# B2B_1.net
KiCad netlist of a schematic drawn in Altium Designer
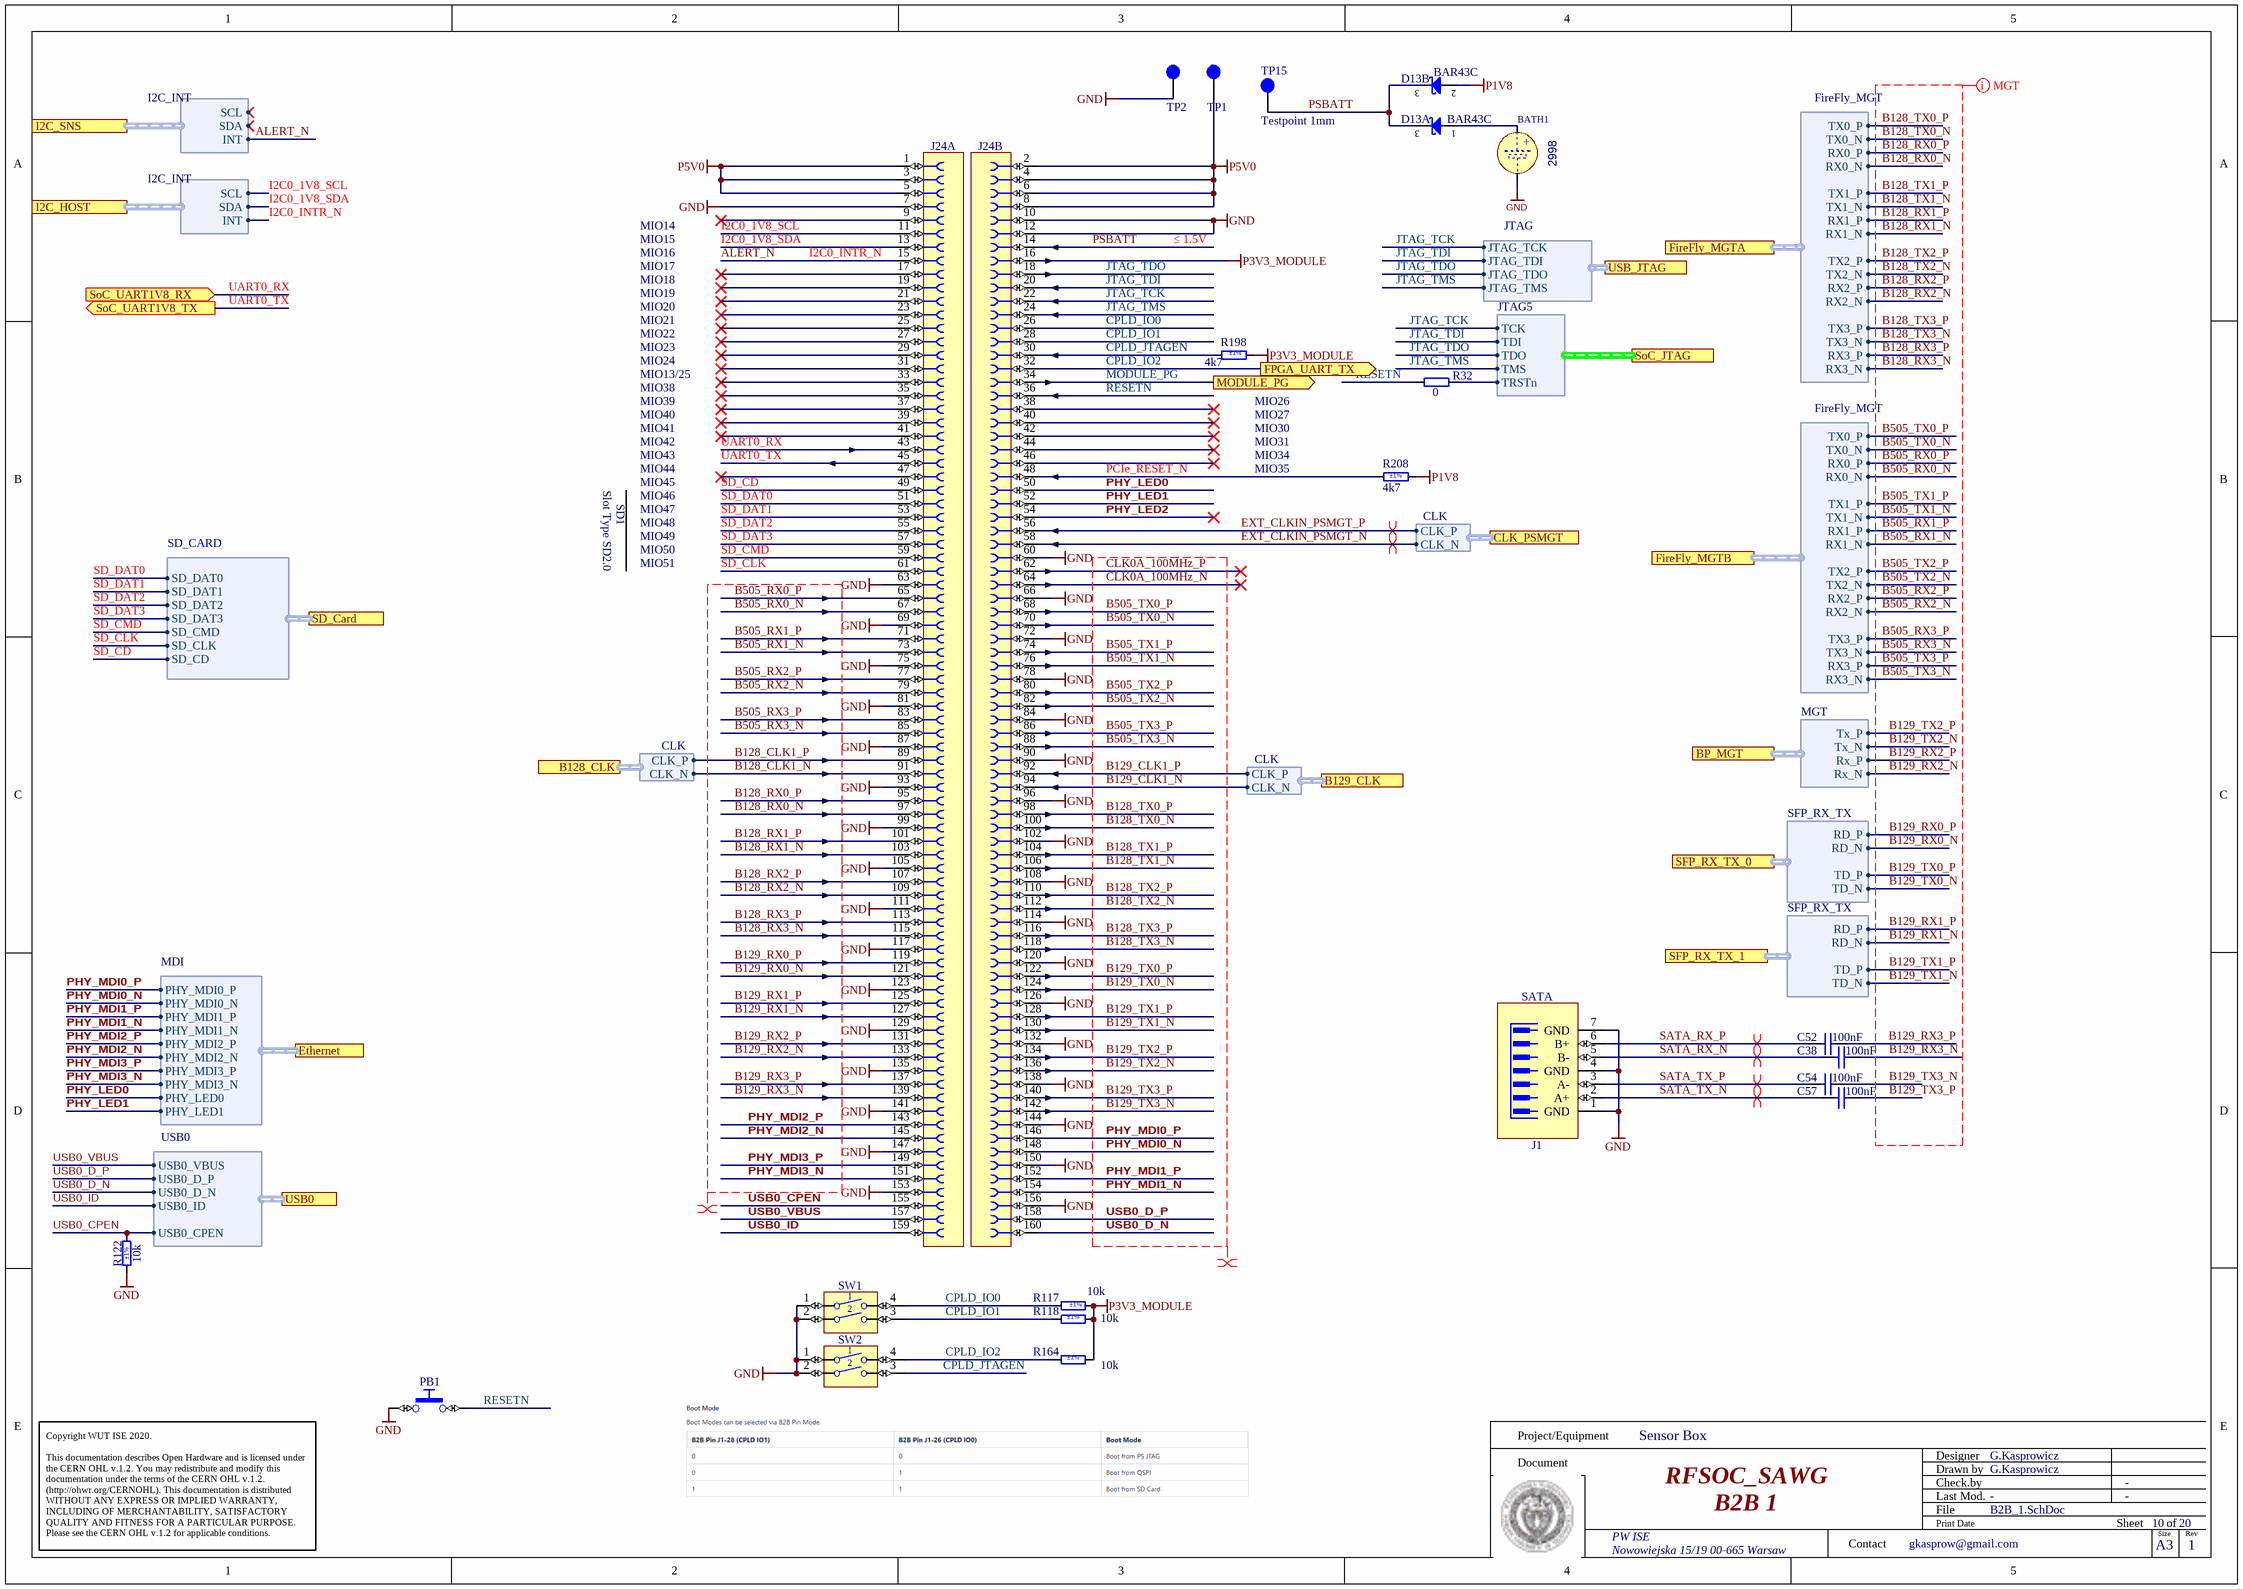
[diagram p0: B2B_1.SchDoc]

(export (version "E")
  (design (tool "Eeschema 10.0.6"))
  (components
    (comp (ref "BATH1")
      (value "~")
      (footprint "BATH_KEYSTONE_2998")
      (description "Battery Holder whit 2 Pin")
      (fields
        (field (name "MANUFACTURER PART NUMBER") "2998")
        (field (name "MANUFACTURER") "KEYSTONE")
        (field (name "PART NUMBER") "BATH_KEYSTONE_2998")
        (field (name "AUTHOR") "CERN DEM JLC")
      )
      (libsource (lib "Eletro-mechanical") (part "Battery Holder 2 Pin"))
    )
    (comp (ref "C38")
      (value "100nF")
      (footprint "CAPC0603X33N")
      (description "Non-polarised capacitor")
      (fields
        (field (name "PART NUMBER") "CC0201_100NF_6.3V_10%_X5R")
        (field (name "VOLTAGE") "6.3V")
        (field (name "AUTHOR") "CERN DEM JLC")
      )
      (libsource (lib "Capacitors") (part "Capacitor - non polarized"))
    )
    (comp (ref "C52")
      (value "100nF")
      (footprint "CAPC0603X33N")
      (description "Non-polarised capacitor")
      (fields
        (field (name "PART NUMBER") "CC0201_100NF_6.3V_10%_X5R")
        (field (name "VOLTAGE") "6.3V")
        (field (name "AUTHOR") "CERN DEM JLC")
      )
      (libsource (lib "Capacitors") (part "Capacitor - non polarized"))
    )
    (comp (ref "C54")
      (value "100nF")
      (footprint "CAPC0603X33N")
      (description "Non-polarised capacitor")
      (fields
        (field (name "PART NUMBER") "CC0201_100NF_6.3V_10%_X5R")
        (field (name "VOLTAGE") "6.3V")
        (field (name "AUTHOR") "CERN DEM JLC")
      )
      (libsource (lib "Capacitors") (part "Capacitor - non polarized"))
    )
    (comp (ref "C57")
      (value "100nF")
      (footprint "CAPC0603X33N")
      (description "Non-polarised capacitor")
      (fields
        (field (name "PART NUMBER") "CC0201_100NF_6.3V_10%_X5R")
        (field (name "VOLTAGE") "6.3V")
        (field (name "AUTHOR") "CERN DEM JLC")
      )
      (libsource (lib "Capacitors") (part "Capacitor - non polarized"))
    )
    (comp (ref "D13")
      (value "BAR43C")
      (footprint "SOT95P240X130-3N")
      (description "Dual Common Cathode Schottky Diodes")
      (fields
        (field (name "VOLTAGE") "30V")
        (field (name "POWER") "200mA")
        (field (name "AUTHOR") "CERN DEM JLC")
      )
      (libsource (lib "ICs And Semiconductors") (part "Diode Schottky x2 A1C3_A2C3"))
    )
    (comp (ref "J1")
      (value "SATA")
      (footprint "MOLEX_67800-5005")
      (description "7 Pin SATA Receptacle")
      (fields
        (field (name "PART NUMBER") "MOLEX_67800-5005")
        (field (name "MANUFACTURER") "MOLEX")
        (field (name "AUTHOR") "CERN DEM MR")
      )
      (libsource (lib "Connectors") (part "Connector SATA 7 Male"))
    )
    (comp (ref "J24")
      (value "Socket 160")
      (footprint "SAMTEC_SS5-80-3.00-L-D-K")
      (description "Connector 160 Female")
      (fields
        (field (name "PART NUMBER") "SAMTEC_SS5-80-3.00-L-D-K")
        (field (name "MANUFACTURER") "SAMTEC")
        (field (name "AUTHOR") "CERN DEM BC")
      )
      (libsource (lib "Connectors") (part "Connector 160 Female"))
    )
    (comp (ref "PB1")
      (value "Push Button")
      (footprint "PB_TYCO_FSMSM")
      (description "Push-Button Switch SPDT")
      (fields
        (field (name "PART NUMBER") "PB_TYCO_FSMSM")
        (field (name "MANUFACTURER") "TYCO ELECTRONICS")
        (field (name "AUTHOR") "CERN DEM JLC")
      )
      (libsource (lib "Eletro-mechanical") (part "PB SPST 1NO-2NO"))
    )
    (comp (ref "R32")
      (value "0")
      (footprint "RESC1005X40N")
      (description "Resistor")
      (fields
        (field (name "PART NUMBER") "R0402_0R_JUMPER")
        (field (name "MANUFACTURER") "GENERIC")
        (field (name "AUTHOR") "CERN DEM JLC")
      )
      (libsource (lib "Resistors") (part "Resistor"))
    )
    (comp (ref "R117")
      (value "10k")
      (footprint "RESC1005X40N")
      (description "Resistor - 1%")
      (fields
        (field (name "TOLERANCE") "±1%")
        (field (name "PART NUMBER") "R0402_10K_1%_0.0625W_100PPM")
        (field (name "POWER") "0.0625W")
        (field (name "AUTHOR") "CERN DEM JLC")
      )
      (libsource (lib "Resistors") (part "Resistor - 1%"))
    )
    (comp (ref "R118")
      (value "10k")
      (footprint "RESC1005X40N")
      (description "Resistor - 1%")
      (fields
        (field (name "TOLERANCE") "±1%")
        (field (name "PART NUMBER") "R0402_10K_1%_0.0625W_100PPM")
        (field (name "POWER") "0.0625W")
        (field (name "AUTHOR") "CERN DEM JLC")
      )
      (libsource (lib "Resistors") (part "Resistor - 1%"))
    )
    (comp (ref "R122")
      (value "10k")
      (footprint "RESC1005X40N")
      (description "Resistor - 1%")
      (fields
        (field (name "TOLERANCE") "±1%")
        (field (name "PART NUMBER") "R0402_10K_1%_0.0625W_100PPM")
        (field (name "POWER") "0.0625W")
        (field (name "AUTHOR") "CERN DEM JLC")
      )
      (libsource (lib "Resistors") (part "Resistor - 1%"))
    )
    (comp (ref "R164")
      (value "10k")
      (footprint "RESC1005X40N")
      (description "Resistor - 1%")
      (fields
        (field (name "TOLERANCE") "±1%")
        (field (name "PART NUMBER") "R0402_10K_1%_0.0625W_100PPM")
        (field (name "POWER") "0.0625W")
        (field (name "AUTHOR") "CERN DEM JLC")
      )
      (libsource (lib "Resistors") (part "Resistor - 1%"))
    )
    (comp (ref "R198")
      (value "4k7")
      (footprint "RESC1005X40N")
      (description "Resistor - 1%")
      (fields
        (field (name "TOLERANCE") "±1%")
        (field (name "PART NUMBER") "R0402_4K7_1%_0.0625W_100PPM")
        (field (name "POWER") "0.0625W")
        (field (name "AUTHOR") "CERN DEM JLC")
      )
      (libsource (lib "Resistors") (part "Resistor - 1%"))
    )
    (comp (ref "R208")
      (value "4k7")
      (footprint "RESC1005X40N")
      (description "Resistor - 1%")
      (fields
        (field (name "TOLERANCE") "±1%")
        (field (name "PART NUMBER") "R0402_4K7_1%_0.0625W_100PPM")
        (field (name "POWER") "0.0625W")
        (field (name "AUTHOR") "CERN DEM JLC")
      )
      (libsource (lib "Resistors") (part "Resistor - 1%"))
    )
    (comp (ref "SW1")
      (value "Switch")
      (footprint "SW_OMRON_A6H-2102")
      (description "2 Ways SPST DIP Switch")
      (fields
        (field (name "PART NUMBER") "SW_OMRON_A6H-2102")
        (field (name "MANUFACTURER") "OMRON")
        (field (name "AUTHOR") "CERN DEM BC")
      )
      (libsource (lib "Eletro-mechanical") (part "SW 2x SPST DIP Switch"))
    )
    (comp (ref "SW2")
      (value "Switch")
      (footprint "SW_OMRON_A6H-2102")
      (description "2 Ways SPST DIP Switch")
      (fields
        (field (name "PART NUMBER") "SW_OMRON_A6H-2102")
        (field (name "MANUFACTURER") "OMRON")
        (field (name "AUTHOR") "CERN DEM BC")
      )
      (libsource (lib "Eletro-mechanical") (part "SW 2x SPST DIP Switch"))
    )
    (comp (ref "TP1") (value "Testpoint 0.8mm") (footprint "TP_0.8mm") (libsource (lib "TE") (part "TP")))
    (comp (ref "TP2") (value "Testpoint 0.8mm") (footprint "TP_0.8mm") (libsource (lib "TE") (part "TP")))
    (comp (ref "TP15") (value "Testpoint 1mm") (footprint "TP_1mm") (libsource (lib "TE") (part "TP")))
  )
  (nets
    (net (code "11") (name "/ALERT_N") (class "Default")
      (node (ref "J24") (pin "15") (pinfunction "15_15") (pintype "bidirectional"))
    )
    (net (code "12") (name "/B128_CLK1_N") (class "Default")
      (node (ref "J24") (pin "91") (pinfunction "91_91") (pintype "bidirectional"))
    )
    (net (code "13") (name "/B128_CLK1_P") (class "Default")
      (node (ref "J24") (pin "89") (pinfunction "89_89") (pintype "bidirectional"))
    )
    (net (code "14") (name "/B128_RX0_N") (class "Default")
      (node (ref "J24") (pin "97") (pinfunction "97_97") (pintype "bidirectional"))
    )
    (net (code "15") (name "/B128_RX0_P") (class "Default")
      (node (ref "J24") (pin "95") (pinfunction "95_95") (pintype "bidirectional"))
    )
    (net (code "16") (name "/B128_RX1_N") (class "Default")
      (node (ref "J24") (pin "103") (pinfunction "103_103") (pintype "bidirectional"))
    )
    (net (code "17") (name "/B128_RX1_P") (class "Default")
      (node (ref "J24") (pin "101") (pinfunction "101_101") (pintype "bidirectional"))
    )
    (net (code "18") (name "/B128_RX2_N") (class "Default")
      (node (ref "J24") (pin "109") (pinfunction "109_109") (pintype "bidirectional"))
    )
    (net (code "19") (name "/B128_RX2_P") (class "Default")
      (node (ref "J24") (pin "107") (pinfunction "107_107") (pintype "bidirectional"))
    )
    (net (code "20") (name "/B128_RX3_N") (class "Default")
      (node (ref "J24") (pin "115") (pinfunction "115_115") (pintype "bidirectional"))
    )
    (net (code "21") (name "/B128_RX3_P") (class "Default")
      (node (ref "J24") (pin "113") (pinfunction "113_113") (pintype "bidirectional"))
    )
    (net (code "22") (name "/B128_TX0_N") (class "Default")
      (node (ref "J24") (pin "100") (pinfunction "100_100") (pintype "bidirectional"))
    )
    (net (code "23") (name "/B128_TX0_P") (class "Default")
      (node (ref "J24") (pin "98") (pinfunction "98_98") (pintype "bidirectional"))
    )
    (net (code "24") (name "/B128_TX1_N") (class "Default")
      (node (ref "J24") (pin "106") (pinfunction "106_106") (pintype "bidirectional"))
    )
    (net (code "25") (name "/B128_TX1_P") (class "Default")
      (node (ref "J24") (pin "104") (pinfunction "104_104") (pintype "bidirectional"))
    )
    (net (code "26") (name "/B128_TX2_N") (class "Default")
      (node (ref "J24") (pin "112") (pinfunction "112_112") (pintype "bidirectional"))
    )
    (net (code "27") (name "/B128_TX2_P") (class "Default")
      (node (ref "J24") (pin "110") (pinfunction "110_110") (pintype "bidirectional"))
    )
    (net (code "28") (name "/B128_TX3_N") (class "Default")
      (node (ref "J24") (pin "118") (pinfunction "118_118") (pintype "bidirectional"))
    )
    (net (code "29") (name "/B128_TX3_P") (class "Default")
      (node (ref "J24") (pin "116") (pinfunction "116_116") (pintype "bidirectional"))
    )
    (net (code "30") (name "/B129_CLK1_N") (class "Default")
      (node (ref "J24") (pin "94") (pinfunction "94_94") (pintype "bidirectional"))
    )
    (net (code "31") (name "/B129_CLK1_P") (class "Default")
      (node (ref "J24") (pin "92") (pinfunction "92_92") (pintype "bidirectional"))
    )
    (net (code "32") (name "/B129_RX0_N") (class "Default")
      (node (ref "J24") (pin "121") (pinfunction "121_121") (pintype "bidirectional"))
    )
    (net (code "33") (name "/B129_RX0_P") (class "Default")
      (node (ref "J24") (pin "119") (pinfunction "119_119") (pintype "bidirectional"))
    )
    (net (code "34") (name "/B129_RX1_N") (class "Default")
      (node (ref "J24") (pin "127") (pinfunction "127_127") (pintype "bidirectional"))
    )
    (net (code "35") (name "/B129_RX1_P") (class "Default")
      (node (ref "J24") (pin "125") (pinfunction "125_125") (pintype "bidirectional"))
    )
    (net (code "36") (name "/B129_RX2_N") (class "Default")
      (node (ref "J24") (pin "133") (pinfunction "133_133") (pintype "bidirectional"))
    )
    (net (code "37") (name "/B129_RX2_P") (class "Default")
      (node (ref "J24") (pin "131") (pinfunction "131_131") (pintype "bidirectional"))
    )
    (net (code "38") (name "/B129_RX3_N") (class "Default")
      (node (ref "C38") (pin "2") (pinfunction "2_2") (pintype "passive"))
      (node (ref "J24") (pin "139") (pinfunction "139_139") (pintype "bidirectional"))
    )
    (net (code "39") (name "/B129_RX3_P") (class "Default")
      (node (ref "C52") (pin "2") (pinfunction "2_2") (pintype "passive"))
      (node (ref "J24") (pin "137") (pinfunction "137_137") (pintype "bidirectional"))
    )
    (net (code "40") (name "/B129_TX0_N") (class "Default")
      (node (ref "J24") (pin "124") (pinfunction "124_124") (pintype "bidirectional"))
    )
    (net (code "41") (name "/B129_TX0_P") (class "Default")
      (node (ref "J24") (pin "122") (pinfunction "122_122") (pintype "bidirectional"))
    )
    (net (code "42") (name "/B129_TX1_N") (class "Default")
      (node (ref "J24") (pin "130") (pinfunction "130_130") (pintype "bidirectional"))
    )
    (net (code "43") (name "/B129_TX1_P") (class "Default")
      (node (ref "J24") (pin "128") (pinfunction "128_128") (pintype "bidirectional"))
    )
    (net (code "44") (name "/B129_TX2_N") (class "Default")
      (node (ref "J24") (pin "136") (pinfunction "136_136") (pintype "bidirectional"))
    )
    (net (code "45") (name "/B129_TX2_P") (class "Default")
      (node (ref "J24") (pin "134") (pinfunction "134_134") (pintype "bidirectional"))
    )
    (net (code "46") (name "/B129_TX3_N") (class "Default")
      (node (ref "C54") (pin "2") (pinfunction "2_2") (pintype "passive"))
      (node (ref "J24") (pin "142") (pinfunction "142_142") (pintype "bidirectional"))
    )
    (net (code "47") (name "/B129_TX3_P") (class "Default")
      (node (ref "C57") (pin "2") (pinfunction "2_2") (pintype "passive"))
      (node (ref "J24") (pin "140") (pinfunction "140_140") (pintype "bidirectional"))
    )
    (net (code "48") (name "/B505_RX0_N") (class "Default")
      (node (ref "J24") (pin "67") (pinfunction "67_67") (pintype "bidirectional"))
    )
    (net (code "49") (name "/B505_RX0_P") (class "Default")
      (node (ref "J24") (pin "65") (pinfunction "65_65") (pintype "bidirectional"))
    )
    (net (code "50") (name "/B505_RX1_N") (class "Default")
      (node (ref "J24") (pin "73") (pinfunction "73_73") (pintype "bidirectional"))
    )
    (net (code "51") (name "/B505_RX1_P") (class "Default")
      (node (ref "J24") (pin "71") (pinfunction "71_71") (pintype "bidirectional"))
    )
    (net (code "52") (name "/B505_RX2_N") (class "Default")
      (node (ref "J24") (pin "79") (pinfunction "79_79") (pintype "bidirectional"))
    )
    (net (code "53") (name "/B505_RX2_P") (class "Default")
      (node (ref "J24") (pin "77") (pinfunction "77_77") (pintype "bidirectional"))
    )
    (net (code "54") (name "/B505_RX3_N") (class "Default")
      (node (ref "J24") (pin "85") (pinfunction "85_85") (pintype "bidirectional"))
    )
    (net (code "55") (name "/B505_RX3_P") (class "Default")
      (node (ref "J24") (pin "83") (pinfunction "83_83") (pintype "bidirectional"))
    )
    (net (code "56") (name "/B505_TX0_N") (class "Default")
      (node (ref "J24") (pin "70") (pinfunction "70_70") (pintype "bidirectional"))
    )
    (net (code "57") (name "/B505_TX0_P") (class "Default")
      (node (ref "J24") (pin "68") (pinfunction "68_68") (pintype "bidirectional"))
    )
    (net (code "58") (name "/B505_TX1_N") (class "Default")
      (node (ref "J24") (pin "76") (pinfunction "76_76") (pintype "bidirectional"))
    )
    (net (code "59") (name "/B505_TX1_P") (class "Default")
      (node (ref "J24") (pin "74") (pinfunction "74_74") (pintype "bidirectional"))
    )
    (net (code "60") (name "/B505_TX2_N") (class "Default")
      (node (ref "J24") (pin "82") (pinfunction "82_82") (pintype "bidirectional"))
    )
    (net (code "61") (name "/B505_TX2_P") (class "Default")
      (node (ref "J24") (pin "80") (pinfunction "80_80") (pintype "bidirectional"))
    )
    (net (code "62") (name "/B505_TX3_N") (class "Default")
      (node (ref "J24") (pin "88") (pinfunction "88_88") (pintype "bidirectional"))
    )
    (net (code "63") (name "/B505_TX3_P") (class "Default")
      (node (ref "J24") (pin "86") (pinfunction "86_86") (pintype "bidirectional"))
    )
    (net (code "64") (name "/CLK0A_100MHz_N") (class "Default")
      (node (ref "J24") (pin "64") (pinfunction "64_64") (pintype "bidirectional+no_connect"))
    )
    (net (code "65") (name "/CLK0A_100MHz_P") (class "Default")
      (node (ref "J24") (pin "62") (pinfunction "62_62") (pintype "bidirectional+no_connect"))
    )
    (net (code "66") (name "/CPLD_IO0") (class "Default")
      (node (ref "J24") (pin "26") (pinfunction "26_26") (pintype "bidirectional"))
      (node (ref "R117") (pin "1") (pinfunction "1_1") (pintype "passive"))
      (node (ref "SW1") (pin "4") (pinfunction "4_4") (pintype "bidirectional"))
    )
    (net (code "67") (name "/CPLD_IO1") (class "Default")
      (node (ref "J24") (pin "28") (pinfunction "28_28") (pintype "bidirectional"))
      (node (ref "R118") (pin "1") (pinfunction "1_1") (pintype "passive"))
      (node (ref "SW1") (pin "3") (pinfunction "3_3") (pintype "bidirectional"))
    )
    (net (code "68") (name "/CPLD_IO2") (class "Default")
      (node (ref "J24") (pin "32") (pinfunction "32_32") (pintype "bidirectional"))
      (node (ref "R164") (pin "1") (pinfunction "1_1") (pintype "passive"))
      (node (ref "SW2") (pin "4") (pinfunction "4_4") (pintype "bidirectional"))
    )
    (net (code "69") (name "/CPLD_JTAGEN") (class "Default")
      (node (ref "J24") (pin "30") (pinfunction "30_30") (pintype "bidirectional"))
      (node (ref "R198") (pin "2") (pinfunction "2_2") (pintype "passive"))
      (node (ref "SW2") (pin "3") (pinfunction "3_3") (pintype "bidirectional"))
    )
    (net (code "70") (name "/EXT_CLKIN_PSMGT_N") (class "Default")
      (node (ref "J24") (pin "58") (pinfunction "58_58") (pintype "bidirectional"))
    )
    (net (code "71") (name "/EXT_CLKIN_PSMGT_P") (class "Default")
      (node (ref "J24") (pin "56") (pinfunction "56_56") (pintype "bidirectional"))
    )
    (net (code "72") (name "/I2C0_1V8_SCL") (class "Default")
      (node (ref "J24") (pin "11") (pinfunction "11_11") (pintype "bidirectional"))
    )
    (net (code "73") (name "/I2C0_1V8_SDA") (class "Default")
      (node (ref "J24") (pin "13") (pinfunction "13_13") (pintype "bidirectional"))
    )
    (net (code "74") (name "/JTAG_TCK") (class "Default")
      (node (ref "J24") (pin "22") (pinfunction "22_22") (pintype "bidirectional"))
    )
    (net (code "75") (name "/JTAG_TDI") (class "Default")
      (node (ref "J24") (pin "20") (pinfunction "20_20") (pintype "bidirectional"))
    )
    (net (code "76") (name "/JTAG_TDO") (class "Default")
      (node (ref "J24") (pin "18") (pinfunction "18_18") (pintype "bidirectional"))
    )
    (net (code "77") (name "/JTAG_TMS") (class "Default")
      (node (ref "J24") (pin "24") (pinfunction "24_24") (pintype "bidirectional"))
    )
    (net (code "78") (name "/MODULE_PG") (class "Default")
      (node (ref "J24") (pin "34") (pinfunction "34_34") (pintype "bidirectional"))
    )
    (net (code "79") (name "/PCIe_RESET_N") (class "Default")
      (node (ref "J24") (pin "48") (pinfunction "48_48") (pintype "bidirectional"))
      (node (ref "R208") (pin "2") (pinfunction "2_2") (pintype "passive"))
    )
    (net (code "80") (name "/PHY_LED0") (class "Default")
      (node (ref "J24") (pin "50") (pinfunction "50_50") (pintype "bidirectional"))
    )
    (net (code "81") (name "/PHY_LED1") (class "Default")
      (node (ref "J24") (pin "52") (pinfunction "52_52") (pintype "bidirectional"))
    )
    (net (code "82") (name "/PHY_LED2") (class "Default")
      (node (ref "J24") (pin "54") (pinfunction "54_54") (pintype "bidirectional+no_connect"))
    )
    (net (code "83") (name "/PHY_MDI0_N") (class "Default")
      (node (ref "J24") (pin "148") (pinfunction "148_148") (pintype "bidirectional"))
    )
    (net (code "84") (name "/PHY_MDI0_P") (class "Default")
      (node (ref "J24") (pin "146") (pinfunction "146_146") (pintype "bidirectional"))
    )
    (net (code "85") (name "/PHY_MDI1_N") (class "Default")
      (node (ref "J24") (pin "154") (pinfunction "154_154") (pintype "bidirectional"))
    )
    (net (code "86") (name "/PHY_MDI1_P") (class "Default")
      (node (ref "J24") (pin "152") (pinfunction "152_152") (pintype "bidirectional"))
    )
    (net (code "87") (name "/PHY_MDI2_N") (class "Default")
      (node (ref "J24") (pin "145") (pinfunction "145_145") (pintype "bidirectional"))
    )
    (net (code "88") (name "/PHY_MDI2_P") (class "Default")
      (node (ref "J24") (pin "143") (pinfunction "143_143") (pintype "bidirectional"))
    )
    (net (code "89") (name "/PHY_MDI3_N") (class "Default")
      (node (ref "J24") (pin "151") (pinfunction "151_151") (pintype "bidirectional"))
    )
    (net (code "90") (name "/PHY_MDI3_P") (class "Default")
      (node (ref "J24") (pin "149") (pinfunction "149_149") (pintype "bidirectional"))
    )
    (net (code "91") (name "/PSBATT") (class "Default")
      (node (ref "D13") (pin "3") (pinfunction "COMC_3") (pintype "passive"))
      (node (ref "J24") (pin "14") (pinfunction "14_14") (pintype "bidirectional"))
      (node (ref "TP15") (pin "1") (pintype "passive"))
    )
    (net (code "92") (name "/RESETN") (class "Default")
      (node (ref "J24") (pin "36") (pinfunction "36_36") (pintype "bidirectional"))
      (node (ref "PB1") (pin "2") (pinfunction "2_2") (pintype "bidirectional"))
      (node (ref "R32") (pin "1") (pinfunction "1_1") (pintype "passive"))
    )
    (net (code "93") (name "/SATA_RX_N") (class "Default")
      (node (ref "C38") (pin "1") (pinfunction "1_1") (pintype "passive"))
      (node (ref "J1") (pin "5") (pinfunction "B-_5") (pintype "bidirectional"))
    )
    (net (code "94") (name "/SATA_RX_P") (class "Default")
      (node (ref "C52") (pin "1") (pinfunction "1_1") (pintype "passive"))
      (node (ref "J1") (pin "6") (pinfunction "B+_6") (pintype "bidirectional"))
    )
    (net (code "95") (name "/SATA_TX_N") (class "Default")
      (node (ref "C57") (pin "1") (pinfunction "1_1") (pintype "passive"))
      (node (ref "J1") (pin "2") (pinfunction "A+_2") (pintype "bidirectional"))
    )
    (net (code "96") (name "/SATA_TX_P") (class "Default")
      (node (ref "C54") (pin "1") (pinfunction "1_1") (pintype "passive"))
      (node (ref "J1") (pin "3") (pinfunction "A-_3") (pintype "bidirectional"))
    )
    (net (code "97") (name "/SD_CD") (class "Default")
      (node (ref "J24") (pin "49") (pinfunction "49_49") (pintype "bidirectional"))
    )
    (net (code "98") (name "/SD_CLK") (class "Default")
      (node (ref "J24") (pin "61") (pinfunction "61_61") (pintype "bidirectional"))
    )
    (net (code "99") (name "/SD_CMD") (class "Default")
      (node (ref "J24") (pin "59") (pinfunction "59_59") (pintype "bidirectional"))
    )
    (net (code "100") (name "/SD_DAT0") (class "Default")
      (node (ref "J24") (pin "51") (pinfunction "51_51") (pintype "bidirectional"))
    )
    (net (code "101") (name "/SD_DAT1") (class "Default")
      (node (ref "J24") (pin "53") (pinfunction "53_53") (pintype "bidirectional"))
    )
    (net (code "102") (name "/SD_DAT2") (class "Default")
      (node (ref "J24") (pin "55") (pinfunction "55_55") (pintype "bidirectional"))
    )
    (net (code "103") (name "/SD_DAT3") (class "Default")
      (node (ref "J24") (pin "57") (pinfunction "57_57") (pintype "bidirectional"))
    )
    (net (code "104") (name "/TRSTn") (class "Default")
      (node (ref "R32") (pin "2") (pinfunction "2_2") (pintype "passive"))
    )
    (net (code "105") (name "/UART0_RX") (class "Default")
      (node (ref "J24") (pin "43") (pinfunction "43_43") (pintype "bidirectional"))
    )
    (net (code "106") (name "/UART0_TX") (class "Default")
      (node (ref "J24") (pin "45") (pinfunction "45_45") (pintype "bidirectional"))
    )
    (net (code "107") (name "/USB0_CPEN") (class "Default")
      (node (ref "J24") (pin "155") (pinfunction "155_155") (pintype "bidirectional"))
      (node (ref "R122") (pin "2") (pinfunction "2_2") (pintype "passive"))
    )
    (net (code "108") (name "/USB0_D_N") (class "Default")
      (node (ref "J24") (pin "160") (pinfunction "160_160") (pintype "bidirectional"))
    )
    (net (code "109") (name "/USB0_D_P") (class "Default")
      (node (ref "J24") (pin "158") (pinfunction "158_158") (pintype "bidirectional"))
    )
    (net (code "110") (name "/USB0_ID") (class "Default")
      (node (ref "J24") (pin "159") (pinfunction "159_159") (pintype "bidirectional"))
    )
    (net (code "111") (name "/USB0_VBUS") (class "Default")
      (node (ref "J24") (pin "157") (pinfunction "157_157") (pintype "bidirectional"))
    )
    (net (code "122") (name "GND") (class "Default")
      (node (ref "BATH1") (pin "2") (pinfunction "MINUS_2") (pintype "power_in"))
      (node (ref "J1") (pin "1") (pinfunction "GND_1") (pintype "power_in"))
      (node (ref "J1") (pin "4") (pinfunction "GND_4") (pintype "power_in"))
      (node (ref "J1") (pin "7") (pinfunction "GND_7") (pintype "power_in"))
      (node (ref "J24") (pin "10") (pinfunction "10_10") (pintype "bidirectional"))
      (node (ref "J24") (pin "102") (pinfunction "102_102") (pintype "bidirectional"))
      (node (ref "J24") (pin "105") (pinfunction "105_105") (pintype "bidirectional"))
      (node (ref "J24") (pin "108") (pinfunction "108_108") (pintype "bidirectional"))
      (node (ref "J24") (pin "111") (pinfunction "111_111") (pintype "bidirectional"))
      (node (ref "J24") (pin "114") (pinfunction "114_114") (pintype "bidirectional"))
      (node (ref "J24") (pin "117") (pinfunction "117_117") (pintype "bidirectional"))
      (node (ref "J24") (pin "12") (pinfunction "12_12") (pintype "bidirectional"))
      (node (ref "J24") (pin "120") (pinfunction "120_120") (pintype "bidirectional"))
      (node (ref "J24") (pin "123") (pinfunction "123_123") (pintype "bidirectional"))
      (node (ref "J24") (pin "126") (pinfunction "126_126") (pintype "bidirectional"))
      (node (ref "J24") (pin "129") (pinfunction "129_129") (pintype "bidirectional"))
      (node (ref "J24") (pin "132") (pinfunction "132_132") (pintype "bidirectional"))
      (node (ref "J24") (pin "135") (pinfunction "135_135") (pintype "bidirectional"))
      (node (ref "J24") (pin "138") (pinfunction "138_138") (pintype "bidirectional"))
      (node (ref "J24") (pin "141") (pinfunction "141_141") (pintype "bidirectional"))
      (node (ref "J24") (pin "144") (pinfunction "144_144") (pintype "bidirectional"))
      (node (ref "J24") (pin "147") (pinfunction "147_147") (pintype "bidirectional"))
      (node (ref "J24") (pin "150") (pinfunction "150_150") (pintype "bidirectional"))
      (node (ref "J24") (pin "153") (pinfunction "153_153") (pintype "bidirectional"))
      (node (ref "J24") (pin "156") (pinfunction "156_156") (pintype "bidirectional"))
      (node (ref "J24") (pin "60") (pinfunction "60_60") (pintype "bidirectional"))
      (node (ref "J24") (pin "63") (pinfunction "63_63") (pintype "bidirectional"))
      (node (ref "J24") (pin "66") (pinfunction "66_66") (pintype "bidirectional"))
      (node (ref "J24") (pin "69") (pinfunction "69_69") (pintype "bidirectional"))
      (node (ref "J24") (pin "7") (pinfunction "7_7") (pintype "bidirectional"))
      (node (ref "J24") (pin "72") (pinfunction "72_72") (pintype "bidirectional"))
      (node (ref "J24") (pin "75") (pinfunction "75_75") (pintype "bidirectional"))
      (node (ref "J24") (pin "78") (pinfunction "78_78") (pintype "bidirectional"))
      (node (ref "J24") (pin "81") (pinfunction "81_81") (pintype "bidirectional"))
      (node (ref "J24") (pin "84") (pinfunction "84_84") (pintype "bidirectional"))
      (node (ref "J24") (pin "87") (pinfunction "87_87") (pintype "bidirectional"))
      (node (ref "J24") (pin "90") (pinfunction "90_90") (pintype "bidirectional"))
      (node (ref "J24") (pin "93") (pinfunction "93_93") (pintype "bidirectional"))
      (node (ref "J24") (pin "96") (pinfunction "96_96") (pintype "bidirectional"))
      (node (ref "J24") (pin "99") (pinfunction "99_99") (pintype "bidirectional"))
      (node (ref "PB1") (pin "1") (pinfunction "1_1") (pintype "bidirectional"))
      (node (ref "R122") (pin "1") (pinfunction "1_1") (pintype "passive"))
      (node (ref "SW1") (pin "1") (pinfunction "1_1") (pintype "bidirectional"))
      (node (ref "SW1") (pin "2") (pinfunction "2_2") (pintype "bidirectional"))
      (node (ref "SW2") (pin "1") (pinfunction "1_1") (pintype "bidirectional"))
      (node (ref "SW2") (pin "2") (pinfunction "2_2") (pintype "bidirectional"))
      (node (ref "TP2") (pin "1") (pintype "passive"))
    )
    (net (code "123") (name "Net-(BATH1-PLUS)") (class "Default")
      (node (ref "BATH1") (pin "1") (pinfunction "PLUS_1") (pintype "power_in"))
      (node (ref "D13") (pin "1") (pinfunction "A_1") (pintype "passive"))
    )
    (net (code "124") (name "P1V8") (class "Default")
      (node (ref "D13") (pin "2") (pinfunction "A_2") (pintype "passive"))
      (node (ref "R208") (pin "1") (pinfunction "1_1") (pintype "passive"))
    )
    (net (code "125") (name "P3V3_MODULE") (class "Default")
      (node (ref "J24") (pin "16") (pinfunction "16_16") (pintype "bidirectional"))
      (node (ref "R117") (pin "2") (pinfunction "2_2") (pintype "passive"))
      (node (ref "R118") (pin "2") (pinfunction "2_2") (pintype "passive"))
      (node (ref "R164") (pin "2") (pinfunction "2_2") (pintype "passive"))
      (node (ref "R198") (pin "1") (pinfunction "1_1") (pintype "passive"))
    )
    (net (code "126") (name "P5V0") (class "Default")
      (node (ref "J24") (pin "1") (pinfunction "1_1") (pintype "bidirectional"))
      (node (ref "J24") (pin "2") (pinfunction "2_2") (pintype "bidirectional"))
      (node (ref "J24") (pin "3") (pinfunction "3_3") (pintype "bidirectional"))
      (node (ref "J24") (pin "4") (pinfunction "4_4") (pintype "bidirectional"))
      (node (ref "J24") (pin "5") (pinfunction "5_5") (pintype "bidirectional"))
      (node (ref "J24") (pin "6") (pinfunction "6_6") (pintype "bidirectional"))
      (node (ref "J24") (pin "8") (pinfunction "8_8") (pintype "bidirectional"))
      (node (ref "TP1") (pin "1") (pintype "passive"))
    )
    (net (code "127") (name "unconnected-(J24-Pad9)") (class "Default")
      (node (ref "J24") (pin "9") (pinfunction "9_9") (pintype "bidirectional+no_connect"))
    )
    (net (code "128") (name "unconnected-(J24-Pad17)") (class "Default")
      (node (ref "J24") (pin "17") (pinfunction "17_17") (pintype "bidirectional+no_connect"))
    )
    (net (code "129") (name "unconnected-(J24-Pad19)") (class "Default")
      (node (ref "J24") (pin "19") (pinfunction "19_19") (pintype "bidirectional+no_connect"))
    )
    (net (code "130") (name "unconnected-(J24-Pad21)") (class "Default")
      (node (ref "J24") (pin "21") (pinfunction "21_21") (pintype "bidirectional+no_connect"))
    )
    (net (code "131") (name "unconnected-(J24-Pad23)") (class "Default")
      (node (ref "J24") (pin "23") (pinfunction "23_23") (pintype "bidirectional+no_connect"))
    )
    (net (code "132") (name "unconnected-(J24-Pad25)") (class "Default")
      (node (ref "J24") (pin "25") (pinfunction "25_25") (pintype "bidirectional+no_connect"))
    )
    (net (code "133") (name "unconnected-(J24-Pad27)") (class "Default")
      (node (ref "J24") (pin "27") (pinfunction "27_27") (pintype "bidirectional+no_connect"))
    )
    (net (code "134") (name "unconnected-(J24-Pad29)") (class "Default")
      (node (ref "J24") (pin "29") (pinfunction "29_29") (pintype "bidirectional+no_connect"))
    )
    (net (code "135") (name "unconnected-(J24-Pad31)") (class "Default")
      (node (ref "J24") (pin "31") (pinfunction "31_31") (pintype "bidirectional+no_connect"))
    )
    (net (code "136") (name "unconnected-(J24-Pad33)") (class "Default")
      (node (ref "J24") (pin "33") (pinfunction "33_33") (pintype "bidirectional+no_connect"))
    )
    (net (code "137") (name "unconnected-(J24-Pad35)") (class "Default")
      (node (ref "J24") (pin "35") (pinfunction "35_35") (pintype "bidirectional+no_connect"))
    )
    (net (code "138") (name "unconnected-(J24-Pad37)") (class "Default")
      (node (ref "J24") (pin "37") (pinfunction "37_37") (pintype "bidirectional+no_connect"))
    )
    (net (code "139") (name "unconnected-(J24-Pad38)") (class "Default")
      (node (ref "J24") (pin "38") (pinfunction "38_38") (pintype "bidirectional+no_connect"))
    )
    (net (code "140") (name "unconnected-(J24-Pad39)") (class "Default")
      (node (ref "J24") (pin "39") (pinfunction "39_39") (pintype "bidirectional+no_connect"))
    )
    (net (code "141") (name "unconnected-(J24-Pad40)") (class "Default")
      (node (ref "J24") (pin "40") (pinfunction "40_40") (pintype "bidirectional+no_connect"))
    )
    (net (code "142") (name "unconnected-(J24-Pad41)") (class "Default")
      (node (ref "J24") (pin "41") (pinfunction "41_41") (pintype "bidirectional+no_connect"))
    )
    (net (code "143") (name "unconnected-(J24-Pad42)") (class "Default")
      (node (ref "J24") (pin "42") (pinfunction "42_42") (pintype "bidirectional+no_connect"))
    )
    (net (code "144") (name "unconnected-(J24-Pad44)") (class "Default")
      (node (ref "J24") (pin "44") (pinfunction "44_44") (pintype "bidirectional+no_connect"))
    )
    (net (code "145") (name "unconnected-(J24-Pad46)") (class "Default")
      (node (ref "J24") (pin "46") (pinfunction "46_46") (pintype "bidirectional+no_connect"))
    )
    (net (code "146") (name "unconnected-(J24-Pad47)") (class "Default")
      (node (ref "J24") (pin "47") (pinfunction "47_47") (pintype "bidirectional+no_connect"))
    )
  )
)
